# interface.net
KiCad netlist of a schematic drawn in Altium Designer
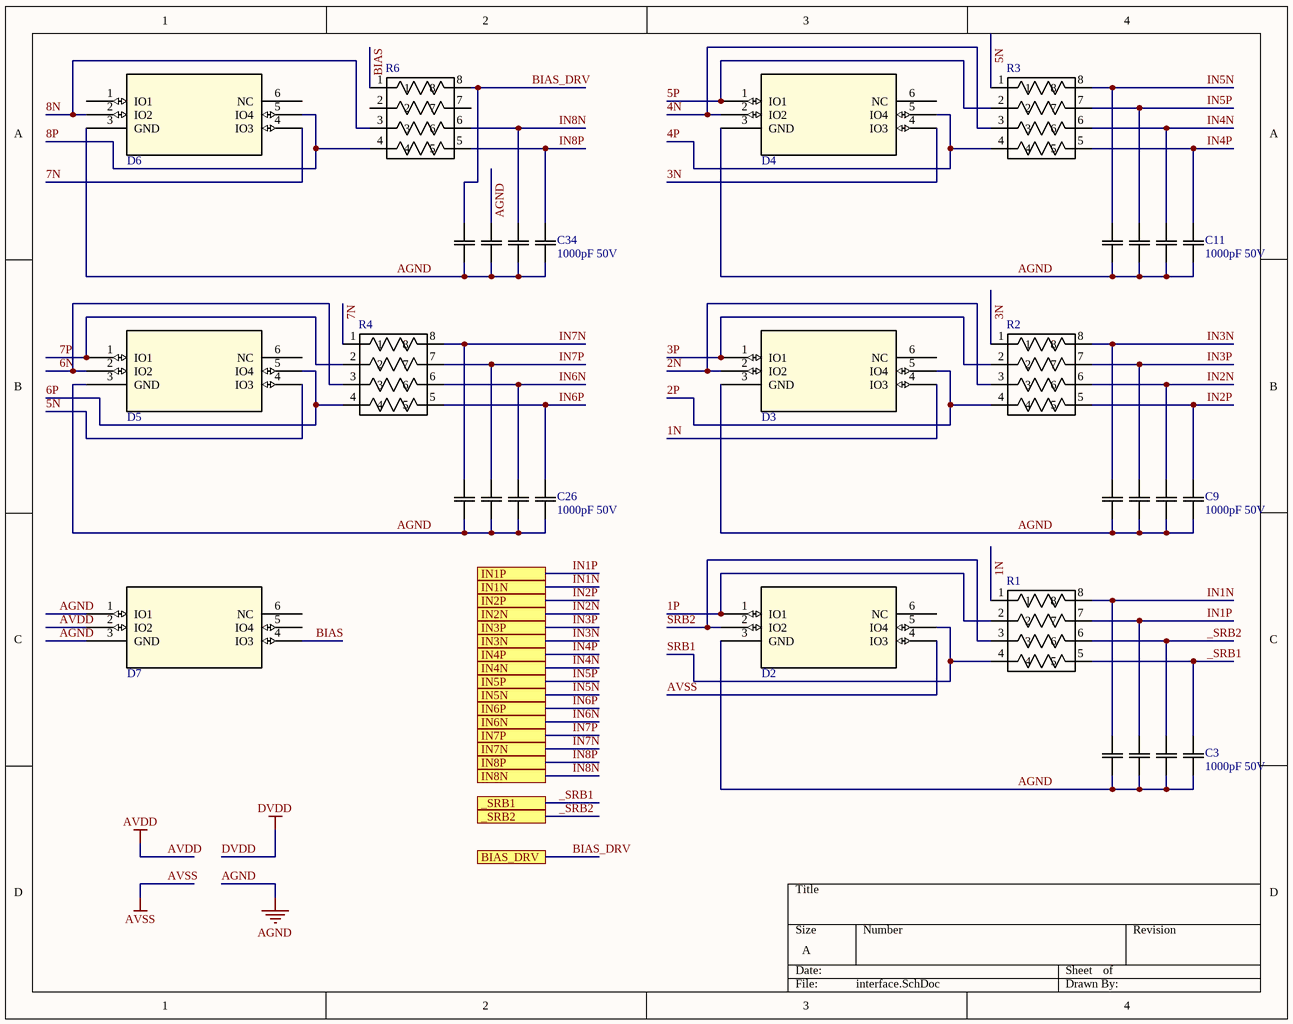
[diagram p0: interface.SchDoc]

(export (version "E")
  (design (tool "Eeschema 10.0.6"))
  (components
    (comp (ref "C3")
      (value "1000pF 50V")
      (description "CAP ARRAY 1000PF 50V X7R 0612")
      (fields (field (name "TOLERANCE") "10%"))
      (libsource (lib "EE_smallOB_BW_v1.0") (part "CA064C102K5RACTU"))
    )
    (comp (ref "C9")
      (value "1000pF 50V")
      (description "CAP ARRAY 1000PF 50V X7R 0612")
      (fields (field (name "TOLERANCE") "10%"))
      (libsource (lib "EE_smallOB_BW_v1.0") (part "CA064C102K5RACTU"))
    )
    (comp (ref "C11")
      (value "1000pF 50V")
      (description "CAP ARRAY 1000PF 50V X7R 0612")
      (fields (field (name "TOLERANCE") "10%"))
      (libsource (lib "EE_smallOB_BW_v1.0") (part "CA064C102K5RACTU"))
    )
    (comp (ref "C26")
      (value "1000pF 50V")
      (description "CAP ARRAY 1000PF 50V X7R 0612")
      (fields (field (name "TOLERANCE") "10%"))
      (libsource (lib "EE_smallOB_BW_v1.0") (part "CA064C102K5RACTU"))
    )
    (comp (ref "C34")
      (value "1000pF 50V")
      (description "CAP ARRAY 1000PF 50V X7R 0612")
      (fields (field (name "TOLERANCE") "10%"))
      (libsource (lib "EE_smallOB_BW_v1.0") (part "CA064C102K5RACTU"))
    )
    (comp (ref "D2")
      (value "TPD4E1B06DCKR")
      (description "TVS DIODE 5.5VWM 14.5VC SC70-6")
      (libsource (lib "EE_smallOB_BW_v1.0") (part "TPD4E1B06DCKR"))
    )
    (comp (ref "D3")
      (value "TPD4E1B06DCKR")
      (description "TVS DIODE 5.5VWM 14.5VC SC70-6")
      (libsource (lib "EE_smallOB_BW_v1.0") (part "TPD4E1B06DCKR"))
    )
    (comp (ref "D4")
      (value "TPD4E1B06DCKR")
      (description "TVS DIODE 5.5VWM 14.5VC SC70-6")
      (libsource (lib "EE_smallOB_BW_v1.0") (part "TPD4E1B06DCKR"))
    )
    (comp (ref "D5")
      (value "TPD4E1B06DCKR")
      (description "TVS DIODE 5.5VWM 14.5VC SC70-6")
      (libsource (lib "EE_smallOB_BW_v1.0") (part "TPD4E1B06DCKR"))
    )
    (comp (ref "D6")
      (value "TPD4E1B06DCKR")
      (description "TVS DIODE 5.5VWM 14.5VC SC70-6")
      (libsource (lib "EE_smallOB_BW_v1.0") (part "TPD4E1B06DCKR"))
    )
    (comp (ref "D7")
      (value "TPD4E1B06DCKR")
      (description "TVS DIODE 5.5VWM 14.5VC SC70-6")
      (libsource (lib "EE_smallOB_BW_v1.0") (part "TPD4E1B06DCKR"))
    )
    (comp (ref "R1")
      (value "CAY16-2201F4LF")
      (description "BOURNS         CAY16-2201F4LF             RESISTOR, ARRAY-4, 2.2KOHM, 5%, SMD")
      (fields (field (name "TOLERANCE") "1%"))
      (libsource (lib "EE_smallOB_BW_v1.0") (part "CAY16-2201F4LF"))
    )
    (comp (ref "R2")
      (value "CAY16-2201F4LF")
      (description "BOURNS         CAY16-2201F4LF             RESISTOR, ARRAY-4, 2.2KOHM, 5%, SMD")
      (fields (field (name "TOLERANCE") "1%"))
      (libsource (lib "EE_smallOB_BW_v1.0") (part "CAY16-2201F4LF"))
    )
    (comp (ref "R3")
      (value "CAY16-2201F4LF")
      (description "BOURNS         CAY16-2201F4LF             RESISTOR, ARRAY-4, 2.2KOHM, 5%, SMD")
      (fields (field (name "TOLERANCE") "1%"))
      (libsource (lib "EE_smallOB_BW_v1.0") (part "CAY16-2201F4LF"))
    )
    (comp (ref "R4")
      (value "CAY16-2201F4LF")
      (description "BOURNS         CAY16-2201F4LF             RESISTOR, ARRAY-4, 2.2KOHM, 5%, SMD")
      (fields (field (name "TOLERANCE") "1%"))
      (libsource (lib "EE_smallOB_BW_v1.0") (part "CAY16-2201F4LF"))
    )
    (comp (ref "R6")
      (value "CAY16-2201F4LF")
      (description "BOURNS         CAY16-2201F4LF             RESISTOR, ARRAY-4, 2.2KOHM, 5%, SMD")
      (fields (field (name "TOLERANCE") "1%"))
      (libsource (lib "EE_smallOB_BW_v1.0") (part "CAY16-2201F4LF"))
    )
  )
  (nets
    (net (code "1") (name "/1N") (class "Default")
      (node (ref "D3") (pin "4") (pinfunction "IO3_4") (pintype "bidirectional"))
      (node (ref "R1") (pin "1") (pinfunction "1_1") (pintype "passive"))
    )
    (net (code "2") (name "/1P") (class "Default")
      (node (ref "D2") (pin "1") (pinfunction "IO1_1") (pintype "bidirectional"))
      (node (ref "R1") (pin "2") (pinfunction "2_2") (pintype "passive"))
    )
    (net (code "3") (name "/2N") (class "Default")
      (node (ref "D3") (pin "2") (pinfunction "IO2_2") (pintype "bidirectional"))
      (node (ref "R2") (pin "3") (pinfunction "3_3") (pintype "passive"))
    )
    (net (code "4") (name "/2P") (class "Default")
      (node (ref "D3") (pin "5") (pinfunction "IO4_5") (pintype "bidirectional"))
      (node (ref "R2") (pin "4") (pinfunction "4_4") (pintype "passive"))
    )
    (net (code "5") (name "/3N") (class "Default")
      (node (ref "D4") (pin "4") (pinfunction "IO3_4") (pintype "bidirectional"))
      (node (ref "R2") (pin "1") (pinfunction "1_1") (pintype "passive"))
    )
    (net (code "6") (name "/3P") (class "Default")
      (node (ref "D3") (pin "1") (pinfunction "IO1_1") (pintype "bidirectional"))
      (node (ref "R2") (pin "2") (pinfunction "2_2") (pintype "passive"))
    )
    (net (code "7") (name "/4N") (class "Default")
      (node (ref "D4") (pin "2") (pinfunction "IO2_2") (pintype "bidirectional"))
      (node (ref "R3") (pin "3") (pinfunction "3_3") (pintype "passive"))
    )
    (net (code "8") (name "/4P") (class "Default")
      (node (ref "D4") (pin "5") (pinfunction "IO4_5") (pintype "bidirectional"))
      (node (ref "R3") (pin "4") (pinfunction "4_4") (pintype "passive"))
    )
    (net (code "9") (name "/5N") (class "Default")
      (node (ref "D5") (pin "4") (pinfunction "IO3_4") (pintype "bidirectional"))
      (node (ref "R3") (pin "1") (pinfunction "1_1") (pintype "passive"))
    )
    (net (code "10") (name "/5P") (class "Default")
      (node (ref "D4") (pin "1") (pinfunction "IO1_1") (pintype "bidirectional"))
      (node (ref "R3") (pin "2") (pinfunction "2_2") (pintype "passive"))
    )
    (net (code "11") (name "/6N") (class "Default")
      (node (ref "D5") (pin "2") (pinfunction "IO2_2") (pintype "bidirectional"))
      (node (ref "R4") (pin "3") (pinfunction "3_3") (pintype "passive"))
    )
    (net (code "12") (name "/6P") (class "Default")
      (node (ref "D5") (pin "5") (pinfunction "IO4_5") (pintype "bidirectional"))
      (node (ref "R4") (pin "4") (pinfunction "4_4") (pintype "passive"))
    )
    (net (code "13") (name "/7N") (class "Default")
      (node (ref "D6") (pin "4") (pinfunction "IO3_4") (pintype "bidirectional"))
      (node (ref "R4") (pin "1") (pinfunction "1_1") (pintype "passive"))
    )
    (net (code "14") (name "/7P") (class "Default")
      (node (ref "D5") (pin "1") (pinfunction "IO1_1") (pintype "bidirectional"))
      (node (ref "R4") (pin "2") (pinfunction "2_2") (pintype "passive"))
    )
    (net (code "15") (name "/8N") (class "Default")
      (node (ref "D6") (pin "2") (pinfunction "IO2_2") (pintype "bidirectional"))
      (node (ref "R6") (pin "3") (pinfunction "3_3") (pintype "passive"))
    )
    (net (code "16") (name "/8P") (class "Default")
      (node (ref "D6") (pin "5") (pinfunction "IO4_5") (pintype "bidirectional"))
      (node (ref "R6") (pin "4") (pinfunction "4_4") (pintype "passive"))
    )
    (net (code "17") (name "/BIAS") (class "Default")
      (node (ref "D7") (pin "4") (pinfunction "IO3_4") (pintype "bidirectional"))
      (node (ref "R6") (pin "1") (pinfunction "1_1") (pintype "passive"))
    )
    (net (code "18") (name "/BIAS_DRV") (class "Default")
      (node (ref "C34") (pin "8") (pinfunction "8_8") (pintype "passive"))
      (node (ref "R6") (pin "8") (pinfunction "8_8") (pintype "passive"))
    )
    (net (code "19") (name "/IN1N") (class "Default")
      (node (ref "C3") (pin "8") (pinfunction "8_8") (pintype "passive"))
      (node (ref "R1") (pin "8") (pinfunction "8_8") (pintype "passive"))
    )
    (net (code "20") (name "/IN1P") (class "Default")
      (node (ref "C3") (pin "7") (pinfunction "7_7") (pintype "passive"))
      (node (ref "R1") (pin "7") (pinfunction "7_7") (pintype "passive"))
    )
    (net (code "21") (name "/IN2N") (class "Default")
      (node (ref "C9") (pin "6") (pinfunction "6_6") (pintype "passive"))
      (node (ref "R2") (pin "6") (pinfunction "6_6") (pintype "passive"))
    )
    (net (code "22") (name "/IN2P") (class "Default")
      (node (ref "C9") (pin "5") (pinfunction "5_5") (pintype "passive"))
      (node (ref "R2") (pin "5") (pinfunction "5_5") (pintype "passive"))
    )
    (net (code "23") (name "/IN3N") (class "Default")
      (node (ref "C9") (pin "8") (pinfunction "8_8") (pintype "passive"))
      (node (ref "R2") (pin "8") (pinfunction "8_8") (pintype "passive"))
    )
    (net (code "24") (name "/IN3P") (class "Default")
      (node (ref "C9") (pin "7") (pinfunction "7_7") (pintype "passive"))
      (node (ref "R2") (pin "7") (pinfunction "7_7") (pintype "passive"))
    )
    (net (code "25") (name "/IN4N") (class "Default")
      (node (ref "C11") (pin "6") (pinfunction "6_6") (pintype "passive"))
      (node (ref "R3") (pin "6") (pinfunction "6_6") (pintype "passive"))
    )
    (net (code "26") (name "/IN4P") (class "Default")
      (node (ref "C11") (pin "5") (pinfunction "5_5") (pintype "passive"))
      (node (ref "R3") (pin "5") (pinfunction "5_5") (pintype "passive"))
    )
    (net (code "27") (name "/IN5N") (class "Default")
      (node (ref "C11") (pin "8") (pinfunction "8_8") (pintype "passive"))
      (node (ref "R3") (pin "8") (pinfunction "8_8") (pintype "passive"))
    )
    (net (code "28") (name "/IN5P") (class "Default")
      (node (ref "C11") (pin "7") (pinfunction "7_7") (pintype "passive"))
      (node (ref "R3") (pin "7") (pinfunction "7_7") (pintype "passive"))
    )
    (net (code "29") (name "/IN6N") (class "Default")
      (node (ref "C26") (pin "6") (pinfunction "6_6") (pintype "passive"))
      (node (ref "R4") (pin "6") (pinfunction "6_6") (pintype "passive"))
    )
    (net (code "30") (name "/IN6P") (class "Default")
      (node (ref "C26") (pin "5") (pinfunction "5_5") (pintype "passive"))
      (node (ref "R4") (pin "5") (pinfunction "5_5") (pintype "passive"))
    )
    (net (code "31") (name "/IN7N") (class "Default")
      (node (ref "C26") (pin "8") (pinfunction "8_8") (pintype "passive"))
      (node (ref "R4") (pin "8") (pinfunction "8_8") (pintype "passive"))
    )
    (net (code "32") (name "/IN7P") (class "Default")
      (node (ref "C26") (pin "7") (pinfunction "7_7") (pintype "passive"))
      (node (ref "R4") (pin "7") (pinfunction "7_7") (pintype "passive"))
    )
    (net (code "33") (name "/IN8N") (class "Default")
      (node (ref "C34") (pin "6") (pinfunction "6_6") (pintype "passive"))
      (node (ref "R6") (pin "6") (pinfunction "6_6") (pintype "passive"))
    )
    (net (code "34") (name "/IN8P") (class "Default")
      (node (ref "C34") (pin "5") (pinfunction "5_5") (pintype "passive"))
      (node (ref "R6") (pin "5") (pinfunction "5_5") (pintype "passive"))
    )
    (net (code "35") (name "/SRB1") (class "Default")
      (node (ref "D2") (pin "5") (pinfunction "IO4_5") (pintype "bidirectional"))
      (node (ref "R1") (pin "4") (pinfunction "4_4") (pintype "passive"))
    )
    (net (code "36") (name "/SRB2") (class "Default")
      (node (ref "D2") (pin "2") (pinfunction "IO2_2") (pintype "bidirectional"))
      (node (ref "R1") (pin "3") (pinfunction "3_3") (pintype "passive"))
    )
    (net (code "37") (name "/_SRB1") (class "Default")
      (node (ref "C3") (pin "5") (pinfunction "5_5") (pintype "passive"))
      (node (ref "R1") (pin "5") (pinfunction "5_5") (pintype "passive"))
    )
    (net (code "38") (name "/_SRB2") (class "Default")
      (node (ref "C3") (pin "6") (pinfunction "6_6") (pintype "passive"))
      (node (ref "R1") (pin "6") (pinfunction "6_6") (pintype "passive"))
    )
    (net (code "39") (name "AGND") (class "Default")
      (node (ref "C11") (pin "1") (pinfunction "1_1") (pintype "passive"))
      (node (ref "C11") (pin "2") (pinfunction "2_2") (pintype "passive"))
      (node (ref "C11") (pin "3") (pinfunction "3_3") (pintype "passive"))
      (node (ref "C11") (pin "4") (pinfunction "4_4") (pintype "passive"))
      (node (ref "C26") (pin "1") (pinfunction "1_1") (pintype "passive"))
      (node (ref "C26") (pin "2") (pinfunction "2_2") (pintype "passive"))
      (node (ref "C26") (pin "3") (pinfunction "3_3") (pintype "passive"))
      (node (ref "C26") (pin "4") (pinfunction "4_4") (pintype "passive"))
      (node (ref "C3") (pin "1") (pinfunction "1_1") (pintype "passive"))
      (node (ref "C3") (pin "2") (pinfunction "2_2") (pintype "passive"))
      (node (ref "C3") (pin "3") (pinfunction "3_3") (pintype "passive"))
      (node (ref "C3") (pin "4") (pinfunction "4_4") (pintype "passive"))
      (node (ref "C34") (pin "1") (pinfunction "1_1") (pintype "passive"))
      (node (ref "C34") (pin "2") (pinfunction "2_2") (pintype "passive"))
      (node (ref "C34") (pin "3") (pinfunction "3_3") (pintype "passive"))
      (node (ref "C34") (pin "4") (pinfunction "4_4") (pintype "passive"))
      (node (ref "C34") (pin "7") (pinfunction "7_7") (pintype "passive"))
      (node (ref "C9") (pin "1") (pinfunction "1_1") (pintype "passive"))
      (node (ref "C9") (pin "2") (pinfunction "2_2") (pintype "passive"))
      (node (ref "C9") (pin "3") (pinfunction "3_3") (pintype "passive"))
      (node (ref "C9") (pin "4") (pinfunction "4_4") (pintype "passive"))
      (node (ref "D2") (pin "3") (pinfunction "GND_3") (pintype "power_in"))
      (node (ref "D3") (pin "3") (pinfunction "GND_3") (pintype "power_in"))
      (node (ref "D4") (pin "3") (pinfunction "GND_3") (pintype "power_in"))
      (node (ref "D5") (pin "3") (pinfunction "GND_3") (pintype "power_in"))
      (node (ref "D6") (pin "3") (pinfunction "GND_3") (pintype "power_in"))
      (node (ref "D7") (pin "1") (pinfunction "IO1_1") (pintype "bidirectional"))
      (node (ref "D7") (pin "3") (pinfunction "GND_3") (pintype "power_in"))
    )
    (net (code "40") (name "AVDD") (class "Default")
      (node (ref "D7") (pin "2") (pinfunction "IO2_2") (pintype "bidirectional"))
    )
    (net (code "41") (name "AVSS") (class "Default")
      (node (ref "D2") (pin "4") (pinfunction "IO3_4") (pintype "bidirectional"))
    )
    (net (code "43") (name "unconnected-(D2-NC-Pad6)") (class "Default")
      (node (ref "D2") (pin "6") (pinfunction "NC_6") (pintype "passive"))
    )
    (net (code "44") (name "unconnected-(D3-NC-Pad6)") (class "Default")
      (node (ref "D3") (pin "6") (pinfunction "NC_6") (pintype "passive"))
    )
    (net (code "45") (name "unconnected-(D4-NC-Pad6)") (class "Default")
      (node (ref "D4") (pin "6") (pinfunction "NC_6") (pintype "passive"))
    )
    (net (code "46") (name "unconnected-(D5-NC-Pad6)") (class "Default")
      (node (ref "D5") (pin "6") (pinfunction "NC_6") (pintype "passive"))
    )
    (net (code "47") (name "unconnected-(D6-IO1-Pad1)") (class "Default")
      (node (ref "D6") (pin "1") (pinfunction "IO1_1") (pintype "bidirectional"))
    )
    (net (code "48") (name "unconnected-(D6-NC-Pad6)") (class "Default")
      (node (ref "D6") (pin "6") (pinfunction "NC_6") (pintype "passive"))
    )
    (net (code "49") (name "unconnected-(D7-IO4-Pad5)") (class "Default")
      (node (ref "D7") (pin "5") (pinfunction "IO4_5") (pintype "bidirectional"))
    )
    (net (code "50") (name "unconnected-(D7-NC-Pad6)") (class "Default")
      (node (ref "D7") (pin "6") (pinfunction "NC_6") (pintype "passive"))
    )
    (net (code "51") (name "unconnected-(R6-Pad2)") (class "Default")
      (node (ref "R6") (pin "2") (pinfunction "2_2") (pintype "passive"))
    )
    (net (code "52") (name "unconnected-(R6-Pad7)") (class "Default")
      (node (ref "R6") (pin "7") (pinfunction "7_7") (pintype "passive"))
    )
  )
)
